# DCC_decoder_v1.net
KiCad netlist of a schematic drawn in EAGLE
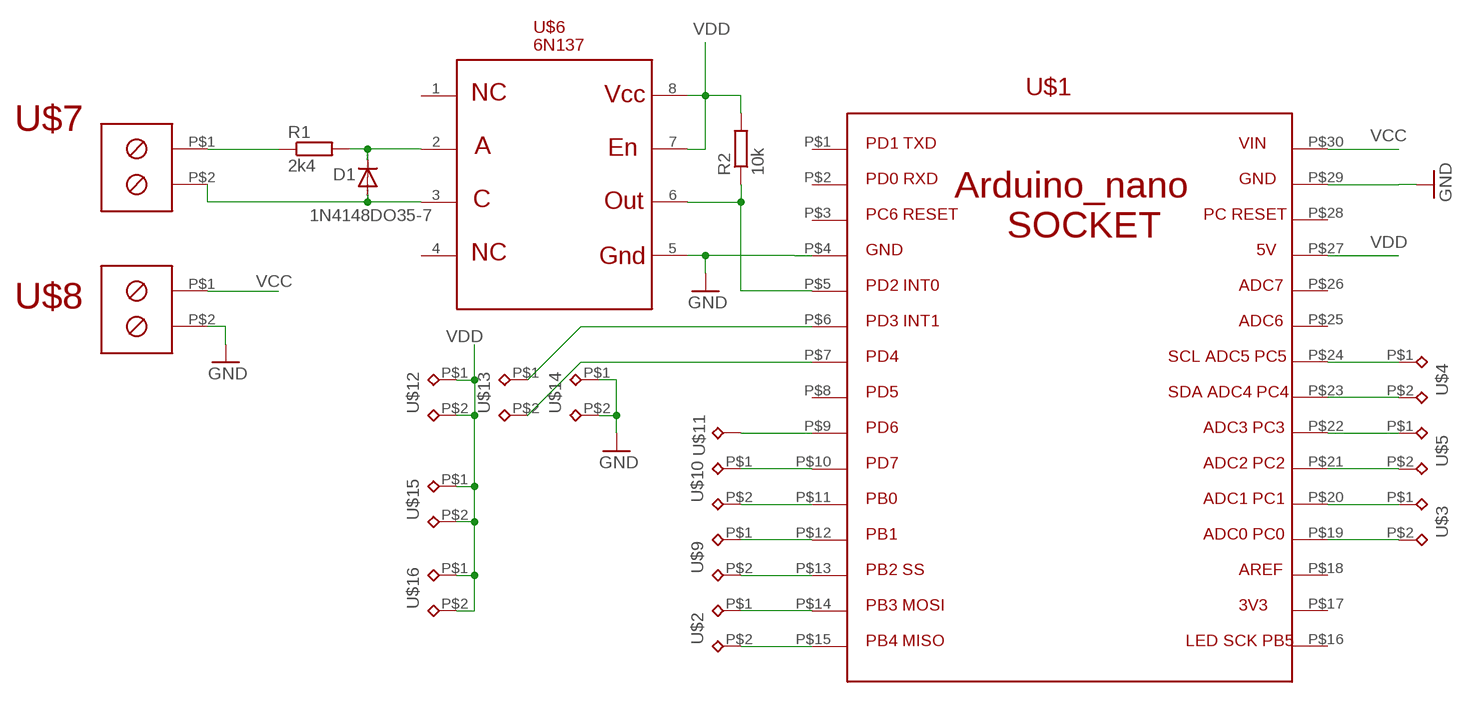
[diagram p0: schematic, sheet 1]

(export (version "E")
  (design (tool "Eeschema 10.0.6"))
  (components
    (comp (ref "D1")
      (value "1N4148DO35-7")
      (footprint "eagle-import:DO35-7")
      (libsource (lib "eagle-import") (part "1N4148DO35-7"))
    )
    (comp (ref "R1")
      (value "2k4")
      (footprint "eagle-import:0207_2V")
      (libsource (lib "eagle-import") (part "R-EU_0207/2V"))
    )
    (comp (ref "R2")
      (value "10k")
      (footprint "eagle-import:0207_2V")
      (libsource (lib "eagle-import") (part "R-EU_0207/2V"))
    )
    (comp (ref "U$1")
      (value "ARD_NANO_SOCKET")
      (footprint "eagle-import:ARD_NANO_SOCKET")
      (libsource (lib "eagle-import") (part "ARD_NANO_SOCKET"))
    )
    (comp (ref "U$2")
      (value "TP_2")
      (footprint "eagle-import:TESTPAD_2")
      (libsource (lib "eagle-import") (part "TP_2"))
    )
    (comp (ref "U$3")
      (value "TP_2")
      (footprint "eagle-import:TESTPAD_2")
      (libsource (lib "eagle-import") (part "TP_2"))
    )
    (comp (ref "U$4")
      (value "TP_2")
      (footprint "eagle-import:TESTPAD_2")
      (libsource (lib "eagle-import") (part "TP_2"))
    )
    (comp (ref "U$5")
      (value "TP_2")
      (footprint "eagle-import:TESTPAD_2")
      (libsource (lib "eagle-import") (part "TP_2"))
    )
    (comp (ref "U$6")
      (value "6N137")
      (footprint "eagle-import:DIL-8")
      (libsource (lib "eagle-import") (part "6N137"))
    )
    (comp (ref "U$7")
      (value "CON_2PIN")
      (footprint "eagle-import:CON_2PIN")
      (libsource (lib "eagle-import") (part "CON_2PIN"))
    )
    (comp (ref "U$8")
      (value "CON_2PIN")
      (footprint "eagle-import:CON_2PIN")
      (libsource (lib "eagle-import") (part "CON_2PIN"))
    )
    (comp (ref "U$9")
      (value "TP_2")
      (footprint "eagle-import:TESTPAD_2")
      (libsource (lib "eagle-import") (part "TP_2"))
    )
    (comp (ref "U$10")
      (value "TP_2")
      (footprint "eagle-import:TESTPAD_2")
      (libsource (lib "eagle-import") (part "TP_2"))
    )
    (comp (ref "U$11")
      (value "TESTPAD")
      (footprint "eagle-import:TESTPAD")
      (libsource (lib "eagle-import") (part "TESTPAD"))
    )
    (comp (ref "U$12")
      (value "TP_2")
      (footprint "eagle-import:TESTPAD_2")
      (libsource (lib "eagle-import") (part "TP_2"))
    )
    (comp (ref "U$13")
      (value "TP_2")
      (footprint "eagle-import:TESTPAD_2")
      (libsource (lib "eagle-import") (part "TP_2"))
    )
    (comp (ref "U$14")
      (value "TP_2")
      (footprint "eagle-import:TESTPAD_2")
      (libsource (lib "eagle-import") (part "TP_2"))
    )
    (comp (ref "U$15")
      (value "TP_2")
      (footprint "eagle-import:TESTPAD_2")
      (libsource (lib "eagle-import") (part "TP_2"))
    )
    (comp (ref "U$16")
      (value "TP_2")
      (footprint "eagle-import:TESTPAD_2")
      (libsource (lib "eagle-import") (part "TP_2"))
    )
  )
  (nets
    (net (code "1") (name "/VCC") (class "Default")
      (node (ref "U$1") (pin "P$30") (pinfunction "P$30_P$30") (pintype "bidirectional"))
      (node (ref "U$8") (pin "P$1") (pinfunction "P$1_P$1") (pintype "bidirectional"))
    )
    (net (code "2") (name "/VDD") (class "Default")
      (node (ref "R2") (pin "2") (pinfunction "2_2") (pintype "passive"))
      (node (ref "U$1") (pin "P$27") (pinfunction "P$27_P$27") (pintype "bidirectional"))
      (node (ref "U$12") (pin "P$1") (pinfunction "P$1_P$1") (pintype "bidirectional"))
      (node (ref "U$12") (pin "P$2") (pinfunction "P$2_P$2") (pintype "bidirectional"))
      (node (ref "U$15") (pin "P$1") (pinfunction "P$1_P$1") (pintype "bidirectional"))
      (node (ref "U$15") (pin "P$2") (pinfunction "P$2_P$2") (pintype "bidirectional"))
      (node (ref "U$16") (pin "P$1") (pinfunction "P$1_P$1") (pintype "bidirectional"))
      (node (ref "U$16") (pin "P$2") (pinfunction "P$2_P$2") (pintype "bidirectional"))
      (node (ref "U$6") (pin "7") (pinfunction "P$7_7") (pintype "bidirectional"))
      (node (ref "U$6") (pin "8") (pinfunction "P$8_8") (pintype "bidirectional"))
    )
    (net (code "3") (name "GND") (class "Default")
      (node (ref "U$1") (pin "P$29") (pinfunction "P$29_P$29") (pintype "bidirectional"))
      (node (ref "U$1") (pin "P$4") (pinfunction "P$4_P$4") (pintype "bidirectional"))
      (node (ref "U$14") (pin "P$1") (pinfunction "P$1_P$1") (pintype "bidirectional"))
      (node (ref "U$14") (pin "P$2") (pinfunction "P$2_P$2") (pintype "bidirectional"))
      (node (ref "U$6") (pin "5") (pinfunction "P$5_5") (pintype "bidirectional"))
      (node (ref "U$8") (pin "P$2") (pinfunction "P$2_P$2") (pintype "bidirectional"))
    )
    (net (code "4") (name "Net-(R1-Pad1)") (class "Default")
      (node (ref "R1") (pin "1") (pinfunction "1_1") (pintype "passive"))
      (node (ref "U$7") (pin "P$1") (pinfunction "P$1_P$1") (pintype "bidirectional"))
    )
    (net (code "5") (name "Net-(U$1-PadP$6)") (class "Default")
      (node (ref "U$1") (pin "P$6") (pinfunction "P$6_P$6") (pintype "bidirectional"))
      (node (ref "U$13") (pin "P$1") (pinfunction "P$1_P$1") (pintype "bidirectional"))
    )
    (net (code "6") (name "Net-(U$1-PadP$7)") (class "Default")
      (node (ref "U$1") (pin "P$7") (pinfunction "P$7_P$7") (pintype "bidirectional"))
      (node (ref "U$13") (pin "P$2") (pinfunction "P$2_P$2") (pintype "bidirectional"))
    )
    (net (code "7") (name "Net-(U$1-PadP$10)") (class "Default")
      (node (ref "U$1") (pin "P$10") (pinfunction "P$10_P$10") (pintype "bidirectional"))
      (node (ref "U$10") (pin "P$1") (pinfunction "P$1_P$1") (pintype "bidirectional"))
    )
    (net (code "8") (name "Net-(U$1-PadP$11)") (class "Default")
      (node (ref "U$1") (pin "P$11") (pinfunction "P$11_P$11") (pintype "bidirectional"))
      (node (ref "U$10") (pin "P$2") (pinfunction "P$2_P$2") (pintype "bidirectional"))
    )
    (net (code "9") (name "Net-(U$1-PadP$12)") (class "Default")
      (node (ref "U$1") (pin "P$12") (pinfunction "P$12_P$12") (pintype "bidirectional"))
      (node (ref "U$9") (pin "P$1") (pinfunction "P$1_P$1") (pintype "bidirectional"))
    )
    (net (code "10") (name "Net-(U$1-PadP$13)") (class "Default")
      (node (ref "U$1") (pin "P$13") (pinfunction "P$13_P$13") (pintype "bidirectional"))
      (node (ref "U$9") (pin "P$2") (pinfunction "P$2_P$2") (pintype "bidirectional"))
    )
    (net (code "11") (name "Net-(U$1-PadP$14)") (class "Default")
      (node (ref "U$1") (pin "P$14") (pinfunction "P$14_P$14") (pintype "bidirectional"))
      (node (ref "U$2") (pin "P$1") (pinfunction "P$1_P$1") (pintype "bidirectional"))
    )
    (net (code "12") (name "Net-(U$1-PadP$15)") (class "Default")
      (node (ref "U$1") (pin "P$15") (pinfunction "P$15_P$15") (pintype "bidirectional"))
      (node (ref "U$2") (pin "P$2") (pinfunction "P$2_P$2") (pintype "bidirectional"))
    )
    (net (code "13") (name "Net-(U$1-PadP$19)") (class "Default")
      (node (ref "U$1") (pin "P$19") (pinfunction "P$19_P$19") (pintype "bidirectional"))
      (node (ref "U$3") (pin "P$2") (pinfunction "P$2_P$2") (pintype "bidirectional"))
    )
    (net (code "14") (name "Net-(U$1-PadP$20)") (class "Default")
      (node (ref "U$1") (pin "P$20") (pinfunction "P$20_P$20") (pintype "bidirectional"))
      (node (ref "U$3") (pin "P$1") (pinfunction "P$1_P$1") (pintype "bidirectional"))
    )
    (net (code "15") (name "Net-(U$1-PadP$21)") (class "Default")
      (node (ref "U$1") (pin "P$21") (pinfunction "P$21_P$21") (pintype "bidirectional"))
      (node (ref "U$5") (pin "P$2") (pinfunction "P$2_P$2") (pintype "bidirectional"))
    )
    (net (code "16") (name "Net-(U$1-PadP$22)") (class "Default")
      (node (ref "U$1") (pin "P$22") (pinfunction "P$22_P$22") (pintype "bidirectional"))
      (node (ref "U$5") (pin "P$1") (pinfunction "P$1_P$1") (pintype "bidirectional"))
    )
    (net (code "17") (name "Net-(U$1-PadP$23)") (class "Default")
      (node (ref "U$1") (pin "P$23") (pinfunction "P$23_P$23") (pintype "bidirectional"))
      (node (ref "U$4") (pin "P$2") (pinfunction "P$2_P$2") (pintype "bidirectional"))
    )
    (net (code "18") (name "Net-(U$1-PadP$24)") (class "Default")
      (node (ref "U$1") (pin "P$24") (pinfunction "P$24_P$24") (pintype "bidirectional"))
      (node (ref "U$4") (pin "P$1") (pinfunction "P$1_P$1") (pintype "bidirectional"))
    )
    (net (code "19") (name "Net-(U$6-P$2)") (class "Default")
      (node (ref "D1") (pin "C") (pinfunction "C_C") (pintype "passive"))
      (node (ref "R1") (pin "2") (pinfunction "2_2") (pintype "passive"))
      (node (ref "U$6") (pin "2") (pinfunction "P$2_2") (pintype "bidirectional"))
    )
    (net (code "20") (name "Net-(U$6-P$3)") (class "Default")
      (node (ref "D1") (pin "A") (pinfunction "A_A") (pintype "passive"))
      (node (ref "U$6") (pin "3") (pinfunction "P$3_3") (pintype "bidirectional"))
      (node (ref "U$7") (pin "P$2") (pinfunction "P$2_P$2") (pintype "bidirectional"))
    )
    (net (code "21") (name "Net-(U$6-P$6)") (class "Default")
      (node (ref "R2") (pin "1") (pinfunction "1_1") (pintype "passive"))
      (node (ref "U$1") (pin "P$5") (pinfunction "P$5_P$5") (pintype "bidirectional"))
      (node (ref "U$6") (pin "6") (pinfunction "P$6_6") (pintype "bidirectional"))
    )
    (net (code "22") (name "Net-(U$11-TP)") (class "Default")
      (node (ref "U$1") (pin "P$9") (pinfunction "P$9_P$9") (pintype "bidirectional"))
      (node (ref "U$11") (pin "P$1") (pinfunction "TP_P$1") (pintype "input"))
    )
    (net (code "23") (name "unconnected-(U$1-PadP$1)") (class "Default")
      (node (ref "U$1") (pin "P$1") (pinfunction "P$1_P$1") (pintype "bidirectional"))
    )
    (net (code "24") (name "unconnected-(U$1-PadP$2)") (class "Default")
      (node (ref "U$1") (pin "P$2") (pinfunction "P$2_P$2") (pintype "bidirectional"))
    )
    (net (code "25") (name "unconnected-(U$1-PadP$3)") (class "Default")
      (node (ref "U$1") (pin "P$3") (pinfunction "P$3_P$3") (pintype "bidirectional"))
    )
    (net (code "26") (name "unconnected-(U$1-PadP$8)") (class "Default")
      (node (ref "U$1") (pin "P$8") (pinfunction "P$8_P$8") (pintype "bidirectional"))
    )
    (net (code "27") (name "unconnected-(U$1-PadP$16)") (class "Default")
      (node (ref "U$1") (pin "P$16") (pinfunction "P$16_P$16") (pintype "bidirectional"))
    )
    (net (code "28") (name "unconnected-(U$1-PadP$17)") (class "Default")
      (node (ref "U$1") (pin "P$17") (pinfunction "P$17_P$17") (pintype "bidirectional"))
    )
    (net (code "29") (name "unconnected-(U$1-PadP$18)") (class "Default")
      (node (ref "U$1") (pin "P$18") (pinfunction "P$18_P$18") (pintype "bidirectional"))
    )
    (net (code "30") (name "unconnected-(U$1-PadP$25)") (class "Default")
      (node (ref "U$1") (pin "P$25") (pinfunction "P$25_P$25") (pintype "bidirectional"))
    )
    (net (code "31") (name "unconnected-(U$1-PadP$26)") (class "Default")
      (node (ref "U$1") (pin "P$26") (pinfunction "P$26_P$26") (pintype "bidirectional"))
    )
    (net (code "32") (name "unconnected-(U$1-PadP$28)") (class "Default")
      (node (ref "U$1") (pin "P$28") (pinfunction "P$28_P$28") (pintype "bidirectional"))
    )
    (net (code "33") (name "unconnected-(U$6-P$1-Pad1)") (class "Default")
      (node (ref "U$6") (pin "1") (pinfunction "P$1_1") (pintype "bidirectional"))
    )
    (net (code "34") (name "unconnected-(U$6-P$4-Pad4)") (class "Default")
      (node (ref "U$6") (pin "4") (pinfunction "P$4_4") (pintype "bidirectional"))
    )
  )
)
